# cn3302.net
KiCad netlist of a schematic drawn in EAGLE
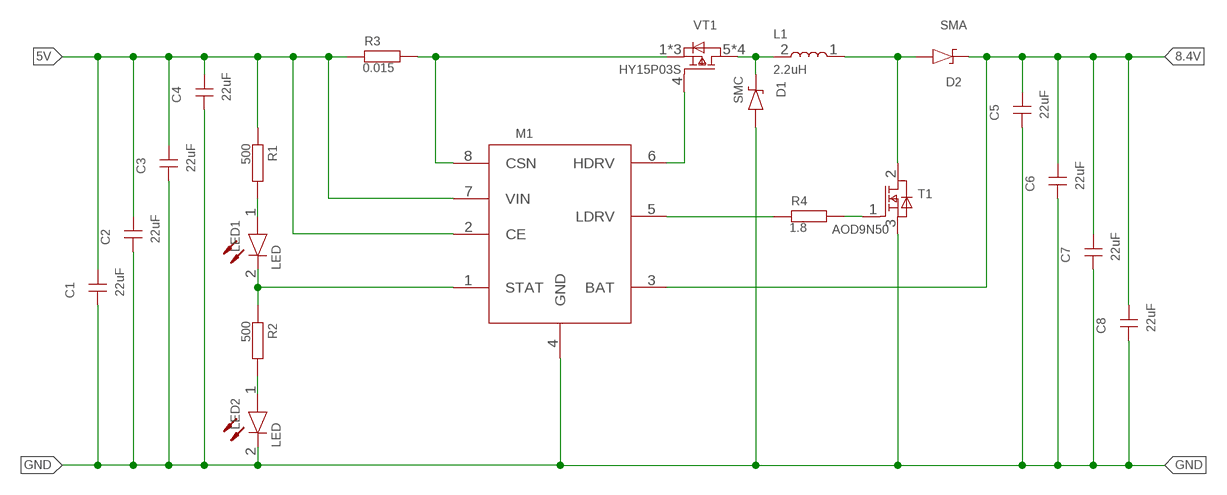
[diagram p0: schematic, sheet 1]

(export (version "E")
  (design (tool "Eeschema 10.0.6"))
  (components
    (comp (ref "C1")
      (value "22uF")
      (footprint "eagle-import:1206")
      (libsource (lib "eagle-import") (part "CAPACITOR"))
    )
    (comp (ref "C2")
      (value "22uF")
      (footprint "eagle-import:1206")
      (libsource (lib "eagle-import") (part "CAPACITOR"))
    )
    (comp (ref "C3")
      (value "22uF")
      (footprint "eagle-import:1206")
      (libsource (lib "eagle-import") (part "CAPACITOR"))
    )
    (comp (ref "C4")
      (value "22uF")
      (footprint "eagle-import:1206")
      (libsource (lib "eagle-import") (part "CAPACITOR"))
    )
    (comp (ref "C5")
      (value "22uF")
      (footprint "eagle-import:1206")
      (libsource (lib "eagle-import") (part "CAPACITOR"))
    )
    (comp (ref "C6")
      (value "22uF")
      (footprint "eagle-import:1206")
      (libsource (lib "eagle-import") (part "CAPACITOR"))
    )
    (comp (ref "C7")
      (value "22uF")
      (footprint "eagle-import:1206")
      (libsource (lib "eagle-import") (part "CAPACITOR"))
    )
    (comp (ref "C8")
      (value "22uF")
      (footprint "eagle-import:1206")
      (libsource (lib "eagle-import") (part "CAPACITOR"))
    )
    (comp (ref "D1")
      (value "SMC")
      (footprint "eagle-import:SMC")
      (libsource (lib "eagle-import") (part "DIODESSMC"))
    )
    (comp (ref "D2")
      (value "SMA")
      (footprint "eagle-import:SMA")
      (libsource (lib "eagle-import") (part "DIODESSMA"))
    )
    (comp (ref "L1")
      (value "2.2uH")
      (footprint "eagle-import:FXL0530")
      (libsource (lib "eagle-import") (part "INDUCTORFXL0530-2R2-M"))
    )
    (comp (ref "LED1")
      (value "LED")
      (footprint "eagle-import:LED")
      (libsource (lib "eagle-import") (part "LED"))
    )
    (comp (ref "LED2")
      (value "LED")
      (footprint "eagle-import:LED")
      (libsource (lib "eagle-import") (part "LED"))
    )
    (comp (ref "M1")
      (value "CN3302SOP-8")
      (footprint "eagle-import:SOP-8")
      (libsource (lib "eagle-import") (part "CN3302SOP-8"))
    )
    (comp (ref "R1")
      (value "500")
      (footprint "eagle-import:0603")
      (libsource (lib "eagle-import") (part "RESISTOR0603"))
    )
    (comp (ref "R2")
      (value "500")
      (footprint "eagle-import:0603")
      (libsource (lib "eagle-import") (part "RESISTOR0603"))
    )
    (comp (ref "R3")
      (value "0.015")
      (footprint "eagle-import:2512")
      (libsource (lib "eagle-import") (part "RESISTOR2512"))
    )
    (comp (ref "R4")
      (value "1.8")
      (footprint "eagle-import:0603")
      (libsource (lib "eagle-import") (part "RESISTOR0603"))
    )
    (comp (ref "T1")
      (value "AOD9N50")
      (footprint "eagle-import:DRACK")
      (libsource (lib "eagle-import") (part "AOD9N50"))
    )
    (comp (ref "VT1")
      (value "HY15P03S")
      (footprint "eagle-import:SOP-8")
      (libsource (lib "eagle-import") (part "HY15P03S"))
    )
  )
  (nets
    (net (code "1") (name "5V") (class "Default")
      (node (ref "C1") (pin "2") (pinfunction "P$2_2") (pintype "bidirectional"))
      (node (ref "C2") (pin "2") (pinfunction "P$2_2") (pintype "bidirectional"))
      (node (ref "C3") (pin "2") (pinfunction "P$2_2") (pintype "bidirectional"))
      (node (ref "C4") (pin "2") (pinfunction "P$2_2") (pintype "bidirectional"))
      (node (ref "M1") (pin "2") (pinfunction "CE_2") (pintype "input"))
      (node (ref "M1") (pin "7") (pinfunction "VIN_7") (pintype "output"))
      (node (ref "R1") (pin "1") (pinfunction "P$1_1") (pintype "bidirectional"))
      (node (ref "R3") (pin "1") (pinfunction "P$1_1") (pintype "bidirectional"))
    )
    (net (code "2") (name "8.4V") (class "Default")
      (node (ref "C5") (pin "2") (pinfunction "P$2_2") (pintype "bidirectional"))
      (node (ref "C6") (pin "2") (pinfunction "P$2_2") (pintype "bidirectional"))
      (node (ref "C7") (pin "2") (pinfunction "P$2_2") (pintype "bidirectional"))
      (node (ref "C8") (pin "2") (pinfunction "P$2_2") (pintype "bidirectional"))
      (node (ref "D2") (pin "2") (pinfunction "C_2") (pintype "output"))
      (node (ref "M1") (pin "3") (pinfunction "BAT_3") (pintype "input"))
    )
    (net (code "3") (name "GND") (class "Default")
      (node (ref "C1") (pin "1") (pinfunction "P$1_1") (pintype "bidirectional"))
      (node (ref "C2") (pin "1") (pinfunction "P$1_1") (pintype "bidirectional"))
      (node (ref "C3") (pin "1") (pinfunction "P$1_1") (pintype "bidirectional"))
      (node (ref "C4") (pin "1") (pinfunction "P$1_1") (pintype "bidirectional"))
      (node (ref "C5") (pin "1") (pinfunction "P$1_1") (pintype "bidirectional"))
      (node (ref "C6") (pin "1") (pinfunction "P$1_1") (pintype "bidirectional"))
      (node (ref "C7") (pin "1") (pinfunction "P$1_1") (pintype "bidirectional"))
      (node (ref "C8") (pin "1") (pinfunction "P$1_1") (pintype "bidirectional"))
      (node (ref "D1") (pin "1") (pinfunction "A_1") (pintype "input"))
      (node (ref "LED2") (pin "2") (pinfunction "CATHODE_2") (pintype "output"))
      (node (ref "M1") (pin "4") (pinfunction "GND_4") (pintype "power_in"))
      (node (ref "T1") (pin "3") (pinfunction "S_3") (pintype "output"))
    )
    (net (code "4") (name "Net-(D1-C)") (class "Default")
      (node (ref "D1") (pin "2") (pinfunction "C_2") (pintype "output"))
      (node (ref "L1") (pin "2") (pinfunction "2_2") (pintype "bidirectional"))
      (node (ref "VT1") (pin "5") (pinfunction "D_5") (pintype "output"))
      (node (ref "VT1") (pin "6") (pinfunction "D_6") (pintype "output"))
      (node (ref "VT1") (pin "7") (pinfunction "D_7") (pintype "output"))
      (node (ref "VT1") (pin "8") (pinfunction "D_8") (pintype "output"))
    )
    (net (code "5") (name "Net-(D2-A)") (class "Default")
      (node (ref "D2") (pin "1") (pinfunction "A_1") (pintype "input"))
      (node (ref "L1") (pin "1") (pinfunction "1_1") (pintype "bidirectional"))
      (node (ref "T1") (pin "2") (pinfunction "D_2") (pintype "input"))
    )
    (net (code "6") (name "Net-(LED1-ANODE)") (class "Default")
      (node (ref "LED1") (pin "1") (pinfunction "ANODE_1") (pintype "input"))
      (node (ref "R1") (pin "2") (pinfunction "P$2_2") (pintype "bidirectional"))
    )
    (net (code "7") (name "Net-(LED1-CATHODE)") (class "Default")
      (node (ref "LED1") (pin "2") (pinfunction "CATHODE_2") (pintype "output"))
      (node (ref "M1") (pin "1") (pinfunction "STAT_1") (pintype "input"))
      (node (ref "R2") (pin "1") (pinfunction "P$1_1") (pintype "bidirectional"))
    )
    (net (code "8") (name "Net-(LED2-ANODE)") (class "Default")
      (node (ref "LED2") (pin "1") (pinfunction "ANODE_1") (pintype "input"))
      (node (ref "R2") (pin "2") (pinfunction "P$2_2") (pintype "bidirectional"))
    )
    (net (code "9") (name "Net-(M1-CSN)") (class "Default")
      (node (ref "M1") (pin "8") (pinfunction "CSN_8") (pintype "output"))
      (node (ref "R3") (pin "2") (pinfunction "P$2_2") (pintype "bidirectional"))
      (node (ref "VT1") (pin "1") (pinfunction "S_1") (pintype "input"))
      (node (ref "VT1") (pin "2") (pinfunction "S_2") (pintype "input"))
      (node (ref "VT1") (pin "3") (pinfunction "S_3") (pintype "input"))
    )
    (net (code "10") (name "Net-(M1-HDRV)") (class "Default")
      (node (ref "M1") (pin "6") (pinfunction "HDRV_6") (pintype "output"))
      (node (ref "VT1") (pin "4") (pinfunction "G_4") (pintype "power_in"))
    )
    (net (code "11") (name "Net-(M1-LDRV)") (class "Default")
      (node (ref "M1") (pin "5") (pinfunction "LDRV_5") (pintype "output"))
      (node (ref "R4") (pin "1") (pinfunction "P$1_1") (pintype "bidirectional"))
    )
    (net (code "12") (name "Net-(R4-P$2)") (class "Default")
      (node (ref "R4") (pin "2") (pinfunction "P$2_2") (pintype "bidirectional"))
      (node (ref "T1") (pin "1") (pinfunction "G_1") (pintype "power_in"))
    )
  )
)
